# motor_control_pcb.net
KiCad netlist of a schematic drawn in EAGLE
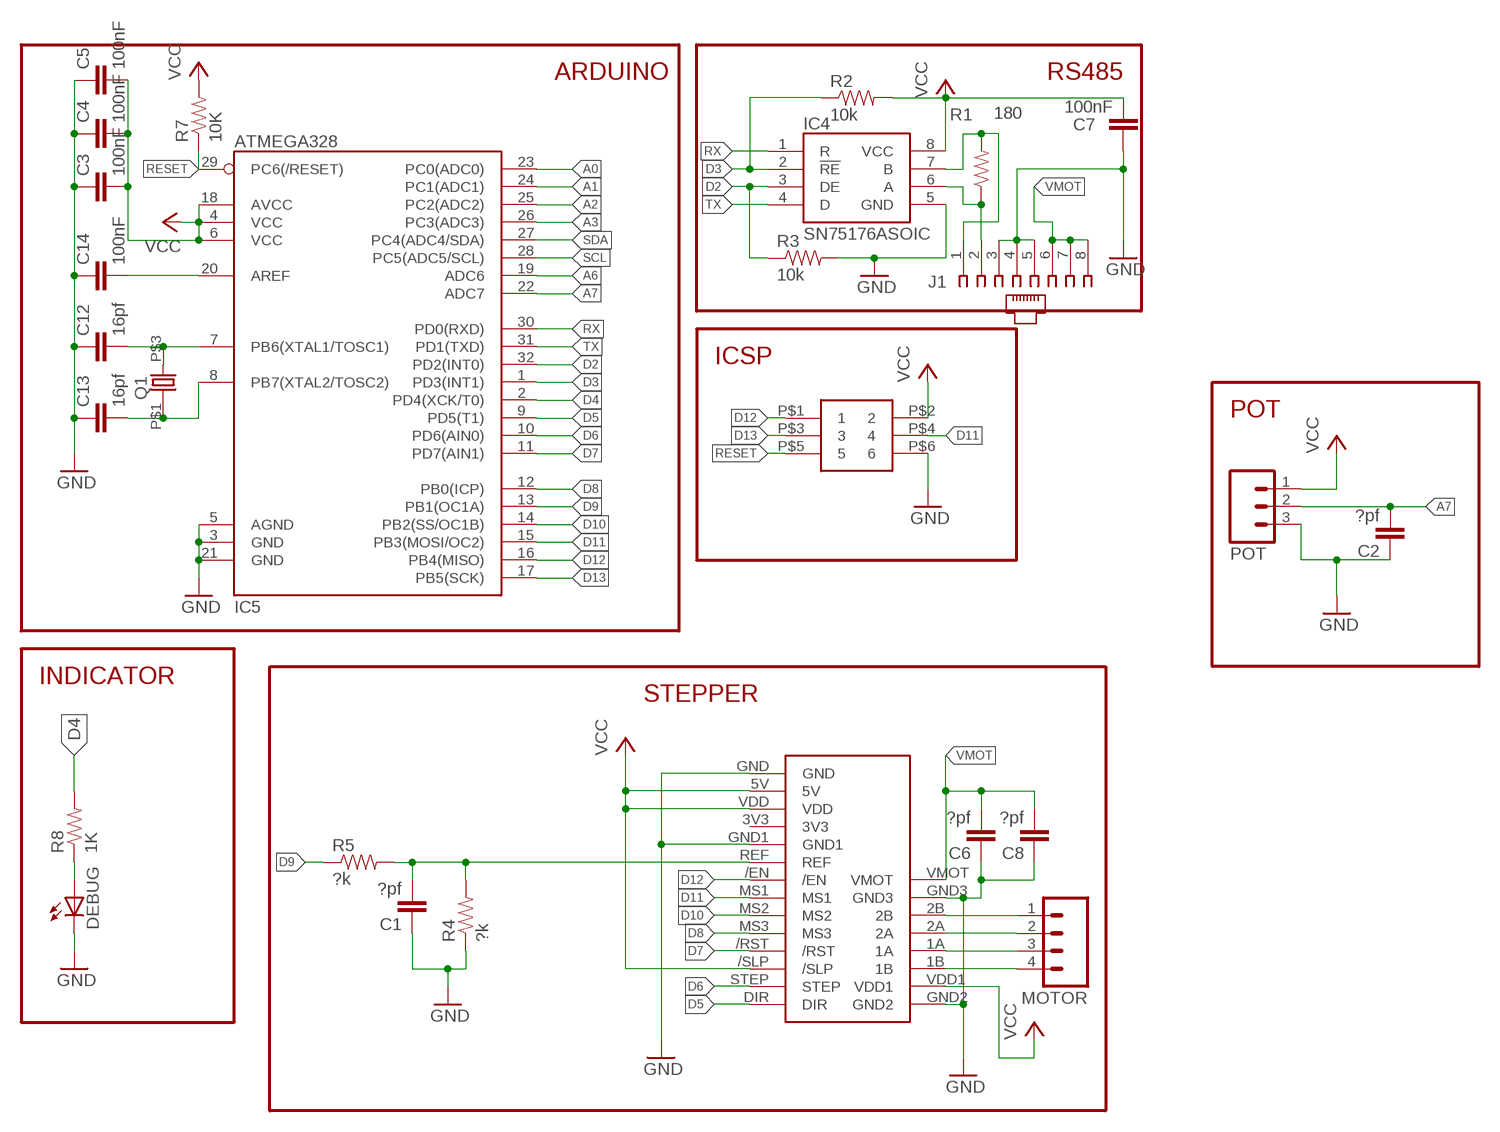
[diagram p0: schematic, sheet 1]

(export (version "E")
  (design (tool "Eeschema 10.0.6"))
  (components
    (comp (ref "C1")
      (value "?pf")
      (footprint "eagle-import:0805")
      (libsource (lib "eagle-import") (part "CAP0805"))
    )
    (comp (ref "C2")
      (value "?pf")
      (footprint "eagle-import:0805")
      (libsource (lib "eagle-import") (part "CAP0805"))
    )
    (comp (ref "C3")
      (value "100nF")
      (footprint "eagle-import:0805")
      (libsource (lib "eagle-import") (part "CAP0805"))
    )
    (comp (ref "C4")
      (value "100nF")
      (footprint "eagle-import:0805")
      (libsource (lib "eagle-import") (part "CAP0805"))
    )
    (comp (ref "C5")
      (value "100nF")
      (footprint "eagle-import:0805")
      (libsource (lib "eagle-import") (part "CAP0805"))
    )
    (comp (ref "C6")
      (value "?pf")
      (footprint "eagle-import:0805")
      (libsource (lib "eagle-import") (part "CAP0805"))
    )
    (comp (ref "C7")
      (value "100nF")
      (footprint "eagle-import:0805")
      (libsource (lib "eagle-import") (part "CAP0805"))
    )
    (comp (ref "C8")
      (value "?pf")
      (footprint "eagle-import:1210")
      (libsource (lib "eagle-import") (part "CAP1210"))
    )
    (comp (ref "C12")
      (value "16pf")
      (footprint "eagle-import:0805")
      (libsource (lib "eagle-import") (part "CAP0805"))
    )
    (comp (ref "C13")
      (value "16pf")
      (footprint "eagle-import:0805")
      (libsource (lib "eagle-import") (part "CAP0805"))
    )
    (comp (ref "C14")
      (value "100nF")
      (footprint "eagle-import:0805")
      (libsource (lib "eagle-import") (part "CAP0805"))
    )
    (comp (ref "DEBUG")
      (value "LED0805")
      (footprint "eagle-import:LED-0805")
      (libsource (lib "eagle-import") (part "LED0805"))
    )
    (comp (ref "IC4")
      (value "SN75176ASOIC")
      (footprint "eagle-import:SO08")
      (libsource (lib "eagle-import") (part "SN75176ASOIC"))
    )
    (comp (ref "IC5")
      (value "ATMEGA328")
      (footprint "eagle-import:TQFP32-08")
      (libsource (lib "eagle-import") (part "ATMEGA168"))
    )
    (comp (ref "J1")
      (value "520426-4")
      (footprint "eagle-import:520426-4")
      (libsource (lib "eagle-import") (part "520426-4"))
    )
    (comp (ref "MOTOR")
      (value "M04PTH")
      (footprint "eagle-import:1X04")
      (libsource (lib "eagle-import") (part "M04PTH"))
    )
    (comp (ref "POT")
      (value "M03PTH")
      (footprint "eagle-import:1X03")
      (libsource (lib "eagle-import") (part "M03PTH"))
    )
    (comp (ref "Q1")
      (value "GLOWBOARD_ABMM2")
      (footprint "eagle-import:GLOWBOARD_ABMM2_CRYSTAL")
      (libsource (lib "eagle-import") (part "GLOWBOARD_ABMM2"))
    )
    (comp (ref "R1")
      (value "180")
      (footprint "eagle-import:0805")
      (libsource (lib "eagle-import") (part "RESISTOR"))
    )
    (comp (ref "R2")
      (value "10k")
      (footprint "eagle-import:0805")
      (libsource (lib "eagle-import") (part "RESISTOR"))
    )
    (comp (ref "R3")
      (value "10k")
      (footprint "eagle-import:0805")
      (libsource (lib "eagle-import") (part "RESISTOR"))
    )
    (comp (ref "R4")
      (value "?k")
      (footprint "eagle-import:0805")
      (libsource (lib "eagle-import") (part "RESISTOR"))
    )
    (comp (ref "R5")
      (value "?k")
      (footprint "eagle-import:0805")
      (libsource (lib "eagle-import") (part "RESISTOR"))
    )
    (comp (ref "R7")
      (value "10K")
      (footprint "eagle-import:0805")
      (libsource (lib "eagle-import") (part "RESISTOR"))
    )
    (comp (ref "R8")
      (value "1K")
      (footprint "eagle-import:0805")
      (libsource (lib "eagle-import") (part "RESISTOR"))
    )
    (comp (ref "U$1")
      (value "POLOLU_DRIVER")
      (footprint "eagle-import:POLOLU_DRIVER")
      (libsource (lib "eagle-import") (part "POLOLU_DRIVER"))
    )
    (comp (ref "U$2")
      (value "2X3HEADER")
      (footprint "eagle-import:2X3HEADER")
      (libsource (lib "eagle-import") (part "2X3HEADER"))
    )
  )
  (nets
    (net (code "1") (name "A0") (class "Default")
      (node (ref "IC5") (pin "23") (pinfunction "PC0(ADC0)_23") (pintype "bidirectional"))
    )
    (net (code "2") (name "A1") (class "Default")
      (node (ref "IC5") (pin "24") (pinfunction "PC1(ADC1)_24") (pintype "bidirectional"))
    )
    (net (code "3") (name "A2") (class "Default")
      (node (ref "IC5") (pin "25") (pinfunction "PC2(ADC2)_25") (pintype "bidirectional"))
    )
    (net (code "4") (name "A3") (class "Default")
      (node (ref "IC5") (pin "26") (pinfunction "PC3(ADC3)_26") (pintype "bidirectional"))
    )
    (net (code "5") (name "A6") (class "Default")
      (node (ref "IC5") (pin "19") (pinfunction "ADC6_19") (pintype "bidirectional"))
    )
    (net (code "6") (name "A7") (class "Default")
      (node (ref "C2") (pin "2") (pinfunction "2_2") (pintype "passive"))
      (node (ref "IC5") (pin "22") (pinfunction "ADC7_22") (pintype "bidirectional"))
      (node (ref "POT") (pin "2") (pinfunction "2_2") (pintype "passive"))
    )
    (net (code "7") (name "D2") (class "Default")
      (node (ref "IC4") (pin "3") (pinfunction "DE_3") (pintype "bidirectional"))
      (node (ref "IC5") (pin "32") (pinfunction "PD2(INT0)_32") (pintype "bidirectional"))
      (node (ref "R3") (pin "1") (pinfunction "1_1") (pintype "passive"))
    )
    (net (code "8") (name "D3") (class "Default")
      (node (ref "IC4") (pin "2") (pinfunction "~{RE}_2") (pintype "bidirectional"))
      (node (ref "IC5") (pin "1") (pinfunction "PD3(INT1)_1") (pintype "bidirectional"))
      (node (ref "R2") (pin "1") (pinfunction "1_1") (pintype "passive"))
    )
    (net (code "9") (name "D4") (class "Default")
      (node (ref "IC5") (pin "2") (pinfunction "PD4(XCK/T0)_2") (pintype "bidirectional"))
      (node (ref "R8") (pin "2") (pinfunction "2_2") (pintype "passive"))
    )
    (net (code "10") (name "D5") (class "Default")
      (node (ref "IC5") (pin "9") (pinfunction "PD5(T1)_9") (pintype "bidirectional"))
      (node (ref "U$1") (pin "DIR") (pinfunction "DIR_DIR") (pintype "bidirectional"))
    )
    (net (code "11") (name "D6") (class "Default")
      (node (ref "IC5") (pin "10") (pinfunction "PD6(AIN0)_10") (pintype "bidirectional"))
      (node (ref "U$1") (pin "STEP") (pinfunction "STEP_STEP") (pintype "bidirectional"))
    )
    (net (code "12") (name "D7") (class "Default")
      (node (ref "IC5") (pin "11") (pinfunction "PD7(AIN1)_11") (pintype "bidirectional"))
      (node (ref "U$1") (pin "/RST") (pinfunction "/RST_/RST") (pintype "bidirectional"))
    )
    (net (code "13") (name "D8") (class "Default")
      (node (ref "IC5") (pin "12") (pinfunction "PB0(ICP)_12") (pintype "bidirectional"))
      (node (ref "U$1") (pin "MS3") (pinfunction "MS3_MS3") (pintype "bidirectional"))
    )
    (net (code "14") (name "D9") (class "Default")
      (node (ref "IC5") (pin "13") (pinfunction "PB1(OC1A)_13") (pintype "bidirectional"))
      (node (ref "R5") (pin "1") (pinfunction "1_1") (pintype "passive"))
    )
    (net (code "15") (name "D10") (class "Default")
      (node (ref "IC5") (pin "14") (pinfunction "PB2(SS/OC1B)_14") (pintype "bidirectional"))
      (node (ref "U$1") (pin "MS2") (pinfunction "MS2_MS2") (pintype "bidirectional"))
    )
    (net (code "16") (name "D11") (class "Default")
      (node (ref "IC5") (pin "15") (pinfunction "PB3(MOSI/OC2)_15") (pintype "bidirectional"))
      (node (ref "U$1") (pin "MS1") (pinfunction "MS1_MS1") (pintype "bidirectional"))
      (node (ref "U$2") (pin "P$4") (pinfunction "4_P$4") (pintype "bidirectional"))
    )
    (net (code "17") (name "D12") (class "Default")
      (node (ref "IC5") (pin "16") (pinfunction "PB4(MISO)_16") (pintype "bidirectional"))
      (node (ref "U$1") (pin "/EN") (pinfunction "/EN_/EN") (pintype "bidirectional"))
      (node (ref "U$2") (pin "P$1") (pinfunction "1_P$1") (pintype "bidirectional"))
    )
    (net (code "18") (name "D13") (class "Default")
      (node (ref "IC5") (pin "17") (pinfunction "PB5(SCK)_17") (pintype "bidirectional"))
      (node (ref "U$2") (pin "P$3") (pinfunction "3_P$3") (pintype "bidirectional"))
    )
    (net (code "19") (name "GND") (class "Default")
      (node (ref "C1") (pin "1") (pinfunction "1_1") (pintype "passive"))
      (node (ref "C12") (pin "1") (pinfunction "1_1") (pintype "passive"))
      (node (ref "C13") (pin "1") (pinfunction "1_1") (pintype "passive"))
      (node (ref "C14") (pin "1") (pinfunction "1_1") (pintype "passive"))
      (node (ref "C2") (pin "1") (pinfunction "1_1") (pintype "passive"))
      (node (ref "C3") (pin "1") (pinfunction "1_1") (pintype "passive"))
      (node (ref "C4") (pin "1") (pinfunction "1_1") (pintype "passive"))
      (node (ref "C5") (pin "1") (pinfunction "1_1") (pintype "passive"))
      (node (ref "C6") (pin "1") (pinfunction "1_1") (pintype "passive"))
      (node (ref "C7") (pin "1") (pinfunction "1_1") (pintype "passive"))
      (node (ref "C8") (pin "1") (pinfunction "1_1") (pintype "passive"))
      (node (ref "DEBUG") (pin "C") (pinfunction "C_C") (pintype "passive"))
      (node (ref "IC4") (pin "5") (pinfunction "GND_5") (pintype "bidirectional"))
      (node (ref "IC5") (pin "21") (pinfunction "GND_21") (pintype "bidirectional"))
      (node (ref "IC5") (pin "3") (pinfunction "GND_3") (pintype "bidirectional"))
      (node (ref "IC5") (pin "5") (pinfunction "AGND_5") (pintype "bidirectional"))
      (node (ref "J1") (pin "3") (pinfunction "3_3") (pintype "passive"))
      (node (ref "J1") (pin "4") (pinfunction "4_4") (pintype "passive"))
      (node (ref "J1") (pin "5") (pinfunction "5_5") (pintype "passive"))
      (node (ref "POT") (pin "3") (pinfunction "3_3") (pintype "passive"))
      (node (ref "R3") (pin "2") (pinfunction "2_2") (pintype "passive"))
      (node (ref "R4") (pin "1") (pinfunction "1_1") (pintype "passive"))
      (node (ref "U$1") (pin "GND") (pinfunction "GND_GND") (pintype "bidirectional"))
      (node (ref "U$1") (pin "GND1") (pinfunction "GND1_GND1") (pintype "bidirectional"))
      (node (ref "U$1") (pin "GND2") (pinfunction "GND2_GND2") (pintype "bidirectional"))
      (node (ref "U$1") (pin "GND3") (pinfunction "GND3_GND3") (pintype "bidirectional"))
      (node (ref "U$2") (pin "P$6") (pinfunction "6_P$6") (pintype "bidirectional"))
    )
    (net (code "20") (name "Net-(C1-Pad2)") (class "Default")
      (node (ref "C1") (pin "2") (pinfunction "2_2") (pintype "passive"))
      (node (ref "R4") (pin "2") (pinfunction "2_2") (pintype "passive"))
      (node (ref "R5") (pin "2") (pinfunction "2_2") (pintype "passive"))
      (node (ref "U$1") (pin "REF") (pinfunction "REF_REF") (pintype "bidirectional"))
    )
    (net (code "21") (name "Net-(DEBUG-PadA)") (class "Default")
      (node (ref "DEBUG") (pin "A") (pinfunction "A_A") (pintype "passive"))
      (node (ref "R8") (pin "1") (pinfunction "1_1") (pintype "passive"))
    )
    (net (code "22") (name "Net-(IC4-A)") (class "Default")
      (node (ref "IC4") (pin "6") (pinfunction "A_6") (pintype "bidirectional"))
      (node (ref "J1") (pin "2") (pinfunction "2_2") (pintype "passive"))
      (node (ref "R1") (pin "1") (pinfunction "1_1") (pintype "passive"))
    )
    (net (code "23") (name "Net-(IC4-B)") (class "Default")
      (node (ref "IC4") (pin "7") (pinfunction "B_7") (pintype "bidirectional"))
      (node (ref "J1") (pin "1") (pinfunction "1_1") (pintype "passive"))
      (node (ref "R1") (pin "2") (pinfunction "2_2") (pintype "passive"))
    )
    (net (code "24") (name "Net-(IC5-AREF)") (class "Default")
      (node (ref "C14") (pin "2") (pinfunction "2_2") (pintype "passive"))
      (node (ref "IC5") (pin "20") (pinfunction "AREF_20") (pintype "bidirectional"))
    )
    (net (code "25") (name "Net-(IC5-PB6(XTAL1{slash}TOSC1))") (class "Default")
      (node (ref "C12") (pin "2") (pinfunction "2_2") (pintype "passive"))
      (node (ref "IC5") (pin "7") (pinfunction "PB6(XTAL1/TOSC1)_7") (pintype "bidirectional"))
      (node (ref "Q1") (pin "P$3") (pinfunction "2_P$3") (pintype "passive"))
    )
    (net (code "26") (name "Net-(IC5-PB7(XTAL2{slash}TOSC2))") (class "Default")
      (node (ref "C13") (pin "2") (pinfunction "2_2") (pintype "passive"))
      (node (ref "IC5") (pin "8") (pinfunction "PB7(XTAL2/TOSC2)_8") (pintype "bidirectional"))
      (node (ref "Q1") (pin "P$1") (pinfunction "1_P$1") (pintype "passive"))
    )
    (net (code "27") (name "Net-(MOTOR-Pad1)") (class "Default")
      (node (ref "MOTOR") (pin "1") (pinfunction "1_1") (pintype "passive"))
      (node (ref "U$1") (pin "2B") (pinfunction "2B_2B") (pintype "bidirectional"))
    )
    (net (code "28") (name "Net-(MOTOR-Pad2)") (class "Default")
      (node (ref "MOTOR") (pin "2") (pinfunction "2_2") (pintype "passive"))
      (node (ref "U$1") (pin "2A") (pinfunction "2A_2A") (pintype "bidirectional"))
    )
    (net (code "29") (name "Net-(MOTOR-Pad3)") (class "Default")
      (node (ref "MOTOR") (pin "3") (pinfunction "3_3") (pintype "passive"))
      (node (ref "U$1") (pin "1A") (pinfunction "1A_1A") (pintype "bidirectional"))
    )
    (net (code "30") (name "Net-(MOTOR-Pad4)") (class "Default")
      (node (ref "MOTOR") (pin "4") (pinfunction "4_4") (pintype "passive"))
      (node (ref "U$1") (pin "1B") (pinfunction "1B_1B") (pintype "bidirectional"))
    )
    (net (code "31") (name "RESET") (class "Default")
      (node (ref "IC5") (pin "29") (pinfunction "PC6(/RESET)_29") (pintype "bidirectional"))
      (node (ref "R7") (pin "1") (pinfunction "1_1") (pintype "passive"))
      (node (ref "U$2") (pin "P$5") (pinfunction "5_P$5") (pintype "bidirectional"))
    )
    (net (code "32") (name "RX") (class "Default")
      (node (ref "IC4") (pin "1") (pinfunction "R_1") (pintype "bidirectional"))
      (node (ref "IC5") (pin "30") (pinfunction "PD0(RXD)_30") (pintype "bidirectional"))
    )
    (net (code "33") (name "SCL") (class "Default")
      (node (ref "IC5") (pin "28") (pinfunction "PC5(ADC5/SCL)_28") (pintype "bidirectional"))
    )
    (net (code "34") (name "SDA") (class "Default")
      (node (ref "IC5") (pin "27") (pinfunction "PC4(ADC4/SDA)_27") (pintype "bidirectional"))
    )
    (net (code "35") (name "TX") (class "Default")
      (node (ref "IC4") (pin "4") (pinfunction "D_4") (pintype "bidirectional"))
      (node (ref "IC5") (pin "31") (pinfunction "PD1(TXD)_31") (pintype "bidirectional"))
    )
    (net (code "36") (name "VCC") (class "Default")
      (node (ref "C3") (pin "2") (pinfunction "2_2") (pintype "passive"))
      (node (ref "C4") (pin "2") (pinfunction "2_2") (pintype "passive"))
      (node (ref "C5") (pin "2") (pinfunction "2_2") (pintype "passive"))
      (node (ref "C7") (pin "2") (pinfunction "2_2") (pintype "passive"))
      (node (ref "IC4") (pin "8") (pinfunction "VCC_8") (pintype "bidirectional"))
      (node (ref "IC5") (pin "18") (pinfunction "AVCC_18") (pintype "bidirectional"))
      (node (ref "IC5") (pin "4") (pinfunction "VCC_4") (pintype "bidirectional"))
      (node (ref "IC5") (pin "6") (pinfunction "VCC_6") (pintype "bidirectional"))
      (node (ref "POT") (pin "1") (pinfunction "1_1") (pintype "passive"))
      (node (ref "R2") (pin "2") (pinfunction "2_2") (pintype "passive"))
      (node (ref "R7") (pin "2") (pinfunction "2_2") (pintype "passive"))
      (node (ref "U$1") (pin "/SLP") (pinfunction "/SLP_/SLP") (pintype "bidirectional"))
      (node (ref "U$1") (pin "5V") (pinfunction "5V_5V") (pintype "bidirectional"))
      (node (ref "U$1") (pin "VDD") (pinfunction "VDD_VDD") (pintype "bidirectional"))
      (node (ref "U$1") (pin "VDD1") (pinfunction "VDD1_VDD1") (pintype "bidirectional"))
      (node (ref "U$2") (pin "P$2") (pinfunction "2_P$2") (pintype "bidirectional"))
    )
    (net (code "37") (name "VMOT") (class "Default")
      (node (ref "C6") (pin "2") (pinfunction "2_2") (pintype "passive"))
      (node (ref "C8") (pin "2") (pinfunction "2_2") (pintype "passive"))
      (node (ref "J1") (pin "6") (pinfunction "6_6") (pintype "passive"))
      (node (ref "J1") (pin "7") (pinfunction "7_7") (pintype "passive"))
      (node (ref "J1") (pin "8") (pinfunction "8_8") (pintype "passive"))
      (node (ref "U$1") (pin "VMOT") (pinfunction "VMOT_VMOT") (pintype "bidirectional"))
    )
    (net (code "38") (name "unconnected-(U$1-Pad3V3)") (class "Default")
      (node (ref "U$1") (pin "3V3") (pinfunction "3V3_3V3") (pintype "bidirectional"))
    )
  )
)
